# temp.net
KiCad netlist of a schematic drawn in EAGLE
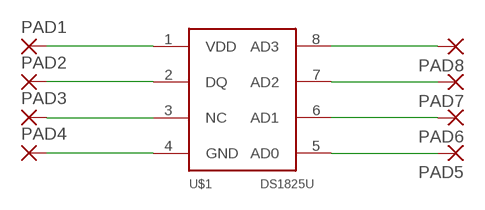
[diagram p0: schematic, sheet 1]

(export (version "E")
  (design (tool "Eeschema 10.0.6"))
  (components
    (comp (ref "PAD1")
      (value "2,15/1,0")
      (footprint "eagle-import:2,15_1,0")
      (libsource (lib "eagle-import") (part "2,15/1,0"))
    )
    (comp (ref "PAD2")
      (value "2,15/1,0")
      (footprint "eagle-import:2,15_1,0")
      (libsource (lib "eagle-import") (part "2,15/1,0"))
    )
    (comp (ref "PAD3")
      (value "2,15/1,0")
      (footprint "eagle-import:2,15_1,0")
      (libsource (lib "eagle-import") (part "2,15/1,0"))
    )
    (comp (ref "PAD4")
      (value "2,15/1,0")
      (footprint "eagle-import:2,15_1,0")
      (libsource (lib "eagle-import") (part "2,15/1,0"))
    )
    (comp (ref "PAD5")
      (value "2,15/1,0")
      (footprint "eagle-import:2,15_1,0")
      (libsource (lib "eagle-import") (part "2,15/1,0"))
    )
    (comp (ref "PAD6")
      (value "2,15/1,0")
      (footprint "eagle-import:2,15_1,0")
      (libsource (lib "eagle-import") (part "2,15/1,0"))
    )
    (comp (ref "PAD7")
      (value "2,15/1,0")
      (footprint "eagle-import:2,15_1,0")
      (libsource (lib "eagle-import") (part "2,15/1,0"))
    )
    (comp (ref "PAD8")
      (value "2,15/1,0")
      (footprint "eagle-import:2,15_1,0")
      (libsource (lib "eagle-import") (part "2,15/1,0"))
    )
    (comp (ref "U$1")
      (value "DS1825U")
      (footprint "eagle-import:UMAX8")
      (libsource (lib "eagle-import") (part "DS1825U"))
    )
  )
  (nets
    (net (code "1") (name "Net-(PAD1-P)") (class "Default")
      (node (ref "PAD1") (pin "1") (pinfunction "P_1") (pintype "passive"))
      (node (ref "U$1") (pin "1") (pinfunction "VDD_1") (pintype "bidirectional"))
    )
    (net (code "2") (name "Net-(PAD2-P)") (class "Default")
      (node (ref "PAD2") (pin "1") (pinfunction "P_1") (pintype "passive"))
      (node (ref "U$1") (pin "2") (pinfunction "DQ_2") (pintype "bidirectional"))
    )
    (net (code "3") (name "Net-(PAD3-P)") (class "Default")
      (node (ref "PAD3") (pin "1") (pinfunction "P_1") (pintype "passive"))
      (node (ref "U$1") (pin "3") (pinfunction "NC_3") (pintype "bidirectional"))
    )
    (net (code "4") (name "Net-(PAD4-P)") (class "Default")
      (node (ref "PAD4") (pin "1") (pinfunction "P_1") (pintype "passive"))
      (node (ref "U$1") (pin "4") (pinfunction "GND_4") (pintype "bidirectional"))
    )
    (net (code "5") (name "Net-(PAD5-P)") (class "Default")
      (node (ref "PAD5") (pin "1") (pinfunction "P_1") (pintype "passive"))
      (node (ref "U$1") (pin "5") (pinfunction "AD0_5") (pintype "bidirectional"))
    )
    (net (code "6") (name "Net-(PAD6-P)") (class "Default")
      (node (ref "PAD6") (pin "1") (pinfunction "P_1") (pintype "passive"))
      (node (ref "U$1") (pin "6") (pinfunction "AD1_6") (pintype "bidirectional"))
    )
    (net (code "7") (name "Net-(PAD7-P)") (class "Default")
      (node (ref "PAD7") (pin "1") (pinfunction "P_1") (pintype "passive"))
      (node (ref "U$1") (pin "7") (pinfunction "AD2_7") (pintype "bidirectional"))
    )
    (net (code "8") (name "Net-(PAD8-P)") (class "Default")
      (node (ref "PAD8") (pin "1") (pinfunction "P_1") (pintype "passive"))
      (node (ref "U$1") (pin "8") (pinfunction "AD3_8") (pintype "bidirectional"))
    )
  )
)
